# Underwater_ROV_RPI.net
KiCad netlist of a schematic drawn in Altium Designer
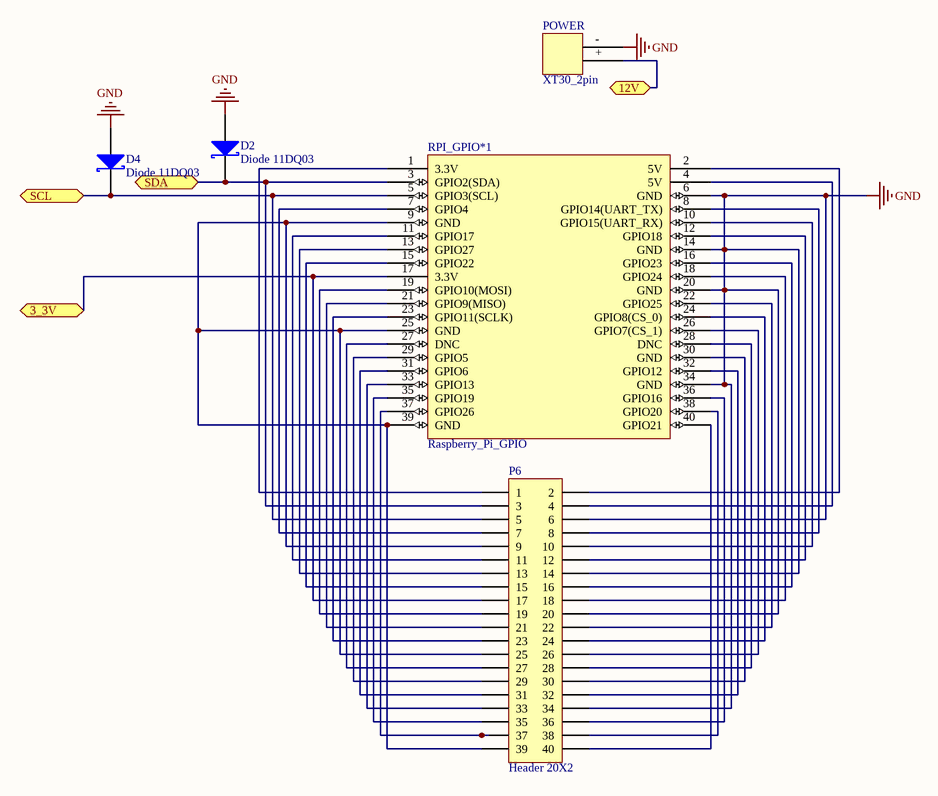
[diagram p0: Underwater_ROV_RPI.SchDoc]

(export (version "E")
  (design (tool "Eeschema 10.0.6"))
  (components
    (comp (ref "D2")
      (value "Diode 11DQ03")
      (footprint "DO-204AL")
      (description "Schottky Rectifier")
      (fields (field (name "PUBLISHER") "Altium Limited"))
      (libsource (lib "Miscellaneous Devices") (part "Diode 11DQ03"))
    )
    (comp (ref "D4")
      (value "Diode 11DQ03")
      (footprint "DO-204AL")
      (description "Schottky Rectifier")
      (fields (field (name "PUBLISHER") "Altium Limited"))
      (libsource (lib "Miscellaneous Devices") (part "Diode 11DQ03"))
    )
    (comp (ref "P6")
      (value "Header 20X2")
      (footprint "HDR2X20")
      (description "Header, 20-Pin, Dual row")
      (fields (field (name "PUBLISHER") "Altium Limited"))
      (libsource (lib "Miscellaneous Connectors") (part "Header 20X2"))
    )
    (comp (ref "POWER")
      (value "XT30_2pin")
      (footprint "XT30_2pin")
      (libsource (lib "UROV_Aux_Lib") (part "XT30_2pin"))
    )
    (comp (ref "RPI_GPIO*1")
      (value "Raspberry_Pi_GPIO")
      (footprint "HDR2X20")
      (libsource (lib "UROV_Aux_Lib") (part "Raspberry_Pi_GPIO"))
    )
  )
  (nets
    (net (code "1") (name "/3_3V") (class "Default")
      (node (ref "P6") (pin "17") (pinfunction "17_17") (pintype "passive"))
      (node (ref "RPI_GPIO*1") (pin "17") (pinfunction "3.3V_17") (pintype "power_in"))
    )
    (net (code "2") (name "/12V") (class "Default") (node (ref "POWER") (pin "+") (pintype "passive")))
    (net (code "3") (name "/SCL") (class "Default")
      (node (ref "D4") (pin "2") (pinfunction "K_2") (pintype "passive"))
      (node (ref "P6") (pin "5") (pinfunction "5_5") (pintype "passive"))
      (node (ref "RPI_GPIO*1") (pin "5") (pinfunction "GPIO3(SCL)_5") (pintype "bidirectional"))
    )
    (net (code "4") (name "/SDA") (class "Default")
      (node (ref "D2") (pin "2") (pinfunction "K_2") (pintype "passive"))
      (node (ref "P6") (pin "3") (pinfunction "3_3") (pintype "passive"))
      (node (ref "RPI_GPIO*1") (pin "3") (pinfunction "GPIO2(SDA)_3") (pintype "bidirectional"))
    )
    (net (code "5") (name "GND") (class "Default")
      (node (ref "D2") (pin "1") (pinfunction "A_1") (pintype "passive"))
      (node (ref "D4") (pin "1") (pinfunction "A_1") (pintype "passive"))
      (node (ref "P6") (pin "14") (pinfunction "14_14") (pintype "passive"))
      (node (ref "P6") (pin "20") (pinfunction "20_20") (pintype "passive"))
      (node (ref "P6") (pin "34") (pinfunction "34_34") (pintype "passive"))
      (node (ref "P6") (pin "6") (pinfunction "6_6") (pintype "passive"))
      (node (ref "POWER") (pin "-") (pintype "passive"))
      (node (ref "RPI_GPIO*1") (pin "14") (pinfunction "GND_14") (pintype "bidirectional"))
      (node (ref "RPI_GPIO*1") (pin "20") (pinfunction "GND_20") (pintype "bidirectional"))
      (node (ref "RPI_GPIO*1") (pin "34") (pinfunction "GND_34") (pintype "bidirectional"))
      (node (ref "RPI_GPIO*1") (pin "6") (pinfunction "GND_6") (pintype "bidirectional"))
    )
    (net (code "6") (name "Net-(P6-Pad1)") (class "Default")
      (node (ref "P6") (pin "1") (pinfunction "1_1") (pintype "passive"))
      (node (ref "RPI_GPIO*1") (pin "1") (pinfunction "3.3V_1") (pintype "power_in"))
    )
    (net (code "7") (name "Net-(P6-Pad2)") (class "Default")
      (node (ref "P6") (pin "2") (pinfunction "2_2") (pintype "passive"))
      (node (ref "RPI_GPIO*1") (pin "2") (pinfunction "5V_2") (pintype "power_in"))
    )
    (net (code "8") (name "Net-(P6-Pad4)") (class "Default")
      (node (ref "P6") (pin "4") (pinfunction "4_4") (pintype "passive"))
      (node (ref "RPI_GPIO*1") (pin "4") (pinfunction "5V_4") (pintype "power_in"))
    )
    (net (code "9") (name "Net-(P6-Pad25)") (class "Default")
      (node (ref "P6") (pin "25") (pinfunction "25_25") (pintype "passive"))
      (node (ref "P6") (pin "39") (pinfunction "39_39") (pintype "passive"))
      (node (ref "P6") (pin "9") (pinfunction "9_9") (pintype "passive"))
      (node (ref "RPI_GPIO*1") (pin "25") (pinfunction "GND_25") (pintype "bidirectional"))
      (node (ref "RPI_GPIO*1") (pin "39") (pinfunction "GND_39") (pintype "bidirectional"))
      (node (ref "RPI_GPIO*1") (pin "9") (pinfunction "GND_9") (pintype "bidirectional"))
    )
    (net (code "10") (name "Net-(P6-Pad27)") (class "Default")
      (node (ref "P6") (pin "27") (pinfunction "27_27") (pintype "passive"))
      (node (ref "RPI_GPIO*1") (pin "27") (pinfunction "DNC_27") (pintype "bidirectional"))
    )
    (net (code "11") (name "Net-(P6-Pad28)") (class "Default")
      (node (ref "P6") (pin "28") (pinfunction "28_28") (pintype "passive"))
      (node (ref "RPI_GPIO*1") (pin "28") (pinfunction "DNC_28") (pintype "bidirectional"))
    )
    (net (code "12") (name "Net-(P6-Pad30)") (class "Default")
      (node (ref "P6") (pin "30") (pinfunction "30_30") (pintype "passive"))
      (node (ref "RPI_GPIO*1") (pin "30") (pinfunction "GND_30") (pintype "bidirectional"))
    )
    (net (code "13") (name "Net-(RPI_GPIO*1-GPIO4)") (class "Default")
      (node (ref "P6") (pin "7") (pinfunction "7_7") (pintype "passive"))
      (node (ref "RPI_GPIO*1") (pin "7") (pinfunction "GPIO4_7") (pintype "bidirectional"))
    )
    (net (code "14") (name "Net-(RPI_GPIO*1-GPIO5)") (class "Default")
      (node (ref "P6") (pin "29") (pinfunction "29_29") (pintype "passive"))
      (node (ref "RPI_GPIO*1") (pin "29") (pinfunction "GPIO5_29") (pintype "bidirectional"))
    )
    (net (code "15") (name "Net-(RPI_GPIO*1-GPIO6)") (class "Default")
      (node (ref "P6") (pin "31") (pinfunction "31_31") (pintype "passive"))
      (node (ref "RPI_GPIO*1") (pin "31") (pinfunction "GPIO6_31") (pintype "bidirectional"))
    )
    (net (code "16") (name "Net-(RPI_GPIO*1-GPIO7(CS_1))") (class "Default")
      (node (ref "P6") (pin "26") (pinfunction "26_26") (pintype "passive"))
      (node (ref "RPI_GPIO*1") (pin "26") (pinfunction "GPIO7(CS_1)_26") (pintype "bidirectional"))
    )
    (net (code "17") (name "Net-(RPI_GPIO*1-GPIO8(CS_0))") (class "Default")
      (node (ref "P6") (pin "24") (pinfunction "24_24") (pintype "passive"))
      (node (ref "RPI_GPIO*1") (pin "24") (pinfunction "GPIO8(CS_0)_24") (pintype "bidirectional"))
    )
    (net (code "18") (name "Net-(RPI_GPIO*1-GPIO9(MISO))") (class "Default")
      (node (ref "P6") (pin "21") (pinfunction "21_21") (pintype "passive"))
      (node (ref "RPI_GPIO*1") (pin "21") (pinfunction "GPIO9(MISO)_21") (pintype "bidirectional"))
    )
    (net (code "19") (name "Net-(RPI_GPIO*1-GPIO10(MOSI))") (class "Default")
      (node (ref "P6") (pin "19") (pinfunction "19_19") (pintype "passive"))
      (node (ref "RPI_GPIO*1") (pin "19") (pinfunction "GPIO10(MOSI)_19") (pintype "bidirectional"))
    )
    (net (code "20") (name "Net-(RPI_GPIO*1-GPIO11(SCLK))") (class "Default")
      (node (ref "P6") (pin "23") (pinfunction "23_23") (pintype "passive"))
      (node (ref "RPI_GPIO*1") (pin "23") (pinfunction "GPIO11(SCLK)_23") (pintype "bidirectional"))
    )
    (net (code "21") (name "Net-(RPI_GPIO*1-GPIO12)") (class "Default")
      (node (ref "P6") (pin "32") (pinfunction "32_32") (pintype "passive"))
      (node (ref "RPI_GPIO*1") (pin "32") (pinfunction "GPIO12_32") (pintype "bidirectional"))
    )
    (net (code "22") (name "Net-(RPI_GPIO*1-GPIO13)") (class "Default")
      (node (ref "P6") (pin "33") (pinfunction "33_33") (pintype "passive"))
      (node (ref "RPI_GPIO*1") (pin "33") (pinfunction "GPIO13_33") (pintype "bidirectional"))
    )
    (net (code "23") (name "Net-(RPI_GPIO*1-GPIO14(UART_TX))") (class "Default")
      (node (ref "P6") (pin "8") (pinfunction "8_8") (pintype "passive"))
      (node (ref "RPI_GPIO*1") (pin "8") (pinfunction "GPIO14(UART_TX)_8") (pintype "bidirectional"))
    )
    (net (code "24") (name "Net-(RPI_GPIO*1-GPIO15(UART_RX))") (class "Default")
      (node (ref "P6") (pin "10") (pinfunction "10_10") (pintype "passive"))
      (node (ref "RPI_GPIO*1") (pin "10") (pinfunction "GPIO15(UART_RX)_10") (pintype "bidirectional"))
    )
    (net (code "25") (name "Net-(RPI_GPIO*1-GPIO16)") (class "Default")
      (node (ref "P6") (pin "36") (pinfunction "36_36") (pintype "passive"))
      (node (ref "RPI_GPIO*1") (pin "36") (pinfunction "GPIO16_36") (pintype "bidirectional"))
    )
    (net (code "26") (name "Net-(RPI_GPIO*1-GPIO17)") (class "Default")
      (node (ref "P6") (pin "11") (pinfunction "11_11") (pintype "passive"))
      (node (ref "RPI_GPIO*1") (pin "11") (pinfunction "GPIO17_11") (pintype "bidirectional"))
    )
    (net (code "27") (name "Net-(RPI_GPIO*1-GPIO18)") (class "Default")
      (node (ref "P6") (pin "12") (pinfunction "12_12") (pintype "passive"))
      (node (ref "RPI_GPIO*1") (pin "12") (pinfunction "GPIO18_12") (pintype "bidirectional"))
    )
    (net (code "28") (name "Net-(RPI_GPIO*1-GPIO19)") (class "Default")
      (node (ref "P6") (pin "35") (pinfunction "35_35") (pintype "passive"))
      (node (ref "RPI_GPIO*1") (pin "35") (pinfunction "GPIO19_35") (pintype "bidirectional"))
    )
    (net (code "29") (name "Net-(RPI_GPIO*1-GPIO20)") (class "Default")
      (node (ref "P6") (pin "38") (pinfunction "38_38") (pintype "passive"))
      (node (ref "RPI_GPIO*1") (pin "38") (pinfunction "GPIO20_38") (pintype "bidirectional"))
    )
    (net (code "30") (name "Net-(RPI_GPIO*1-GPIO21)") (class "Default")
      (node (ref "P6") (pin "40") (pinfunction "40_40") (pintype "passive"))
      (node (ref "RPI_GPIO*1") (pin "40") (pinfunction "GPIO21_40") (pintype "bidirectional"))
    )
    (net (code "31") (name "Net-(RPI_GPIO*1-GPIO22)") (class "Default")
      (node (ref "P6") (pin "15") (pinfunction "15_15") (pintype "passive"))
      (node (ref "RPI_GPIO*1") (pin "15") (pinfunction "GPIO22_15") (pintype "bidirectional"))
    )
    (net (code "32") (name "Net-(RPI_GPIO*1-GPIO23)") (class "Default")
      (node (ref "P6") (pin "16") (pinfunction "16_16") (pintype "passive"))
      (node (ref "RPI_GPIO*1") (pin "16") (pinfunction "GPIO23_16") (pintype "bidirectional"))
    )
    (net (code "33") (name "Net-(RPI_GPIO*1-GPIO24)") (class "Default")
      (node (ref "P6") (pin "18") (pinfunction "18_18") (pintype "passive"))
      (node (ref "RPI_GPIO*1") (pin "18") (pinfunction "GPIO24_18") (pintype "bidirectional"))
    )
    (net (code "34") (name "Net-(RPI_GPIO*1-GPIO25)") (class "Default")
      (node (ref "P6") (pin "22") (pinfunction "22_22") (pintype "passive"))
      (node (ref "RPI_GPIO*1") (pin "22") (pinfunction "GPIO25_22") (pintype "bidirectional"))
    )
    (net (code "35") (name "Net-(RPI_GPIO*1-GPIO26)") (class "Default")
      (node (ref "P6") (pin "37") (pinfunction "37_37") (pintype "passive"))
      (node (ref "RPI_GPIO*1") (pin "37") (pinfunction "GPIO26_37") (pintype "bidirectional"))
    )
    (net (code "36") (name "Net-(RPI_GPIO*1-GPIO27)") (class "Default")
      (node (ref "P6") (pin "13") (pinfunction "13_13") (pintype "passive"))
      (node (ref "RPI_GPIO*1") (pin "13") (pinfunction "GPIO27_13") (pintype "bidirectional"))
    )
  )
)
